# XC7A35TFTG256_bank15.net
KiCad netlist of a schematic drawn in Altium Designer
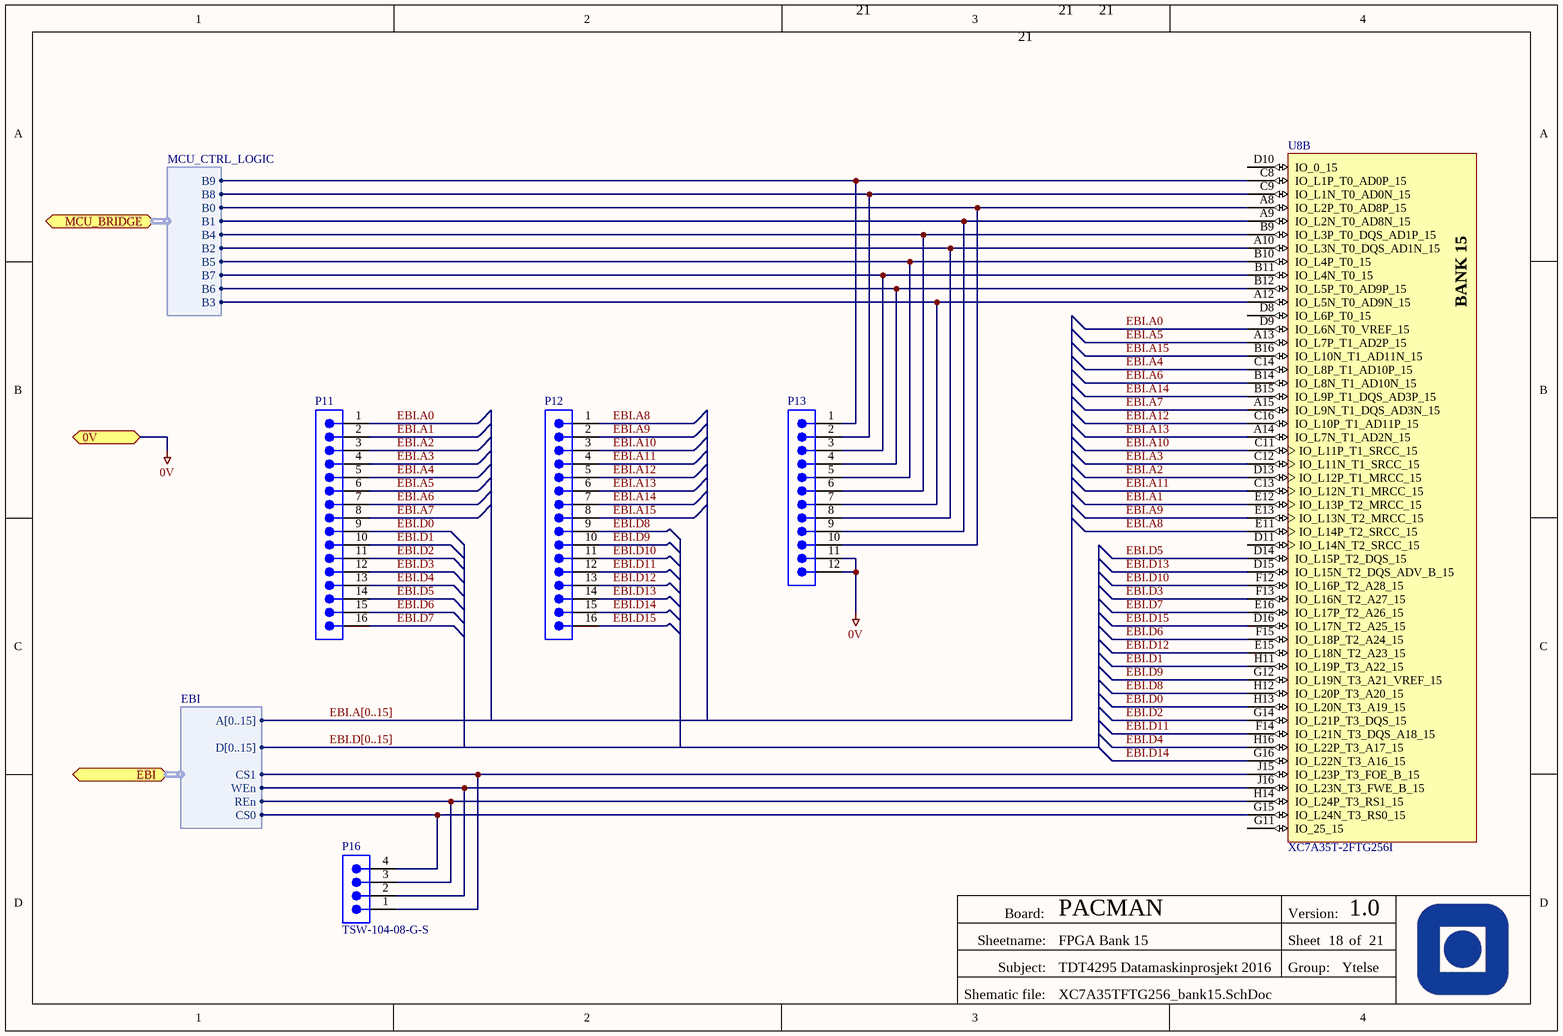
[diagram p0: XC7A35TFTG256_bank15.SchDoc]

(export (version "E")
  (design (tool "Eeschema 10.0.6"))
  (components
    (comp (ref "P11")
      (value "MTLW-116-07-F-S-265")
      (footprint "SMTC-MTLW-116-07-X-S-265")
      (fields (field (name "MANUFACTURER") "Samtec"))
      (libsource (lib "Altium Content Vault") (part "SMTC-MTLW-116-07-X-S-265"))
    )
    (comp (ref "P12")
      (value "MTLW-116-07-F-S-265")
      (footprint "SMTC-MTLW-116-07-X-S-265")
      (fields (field (name "MANUFACTURER") "Samtec"))
      (libsource (lib "Altium Content Vault") (part "SMTC-MTLW-116-07-X-S-265"))
    )
    (comp (ref "P13")
      (value "MTLW-112-07-L-S-125")
      (footprint "SMTC-MTLW-112-07-X-S-125")
      (fields (field (name "MANUFACTURER") "Samtec"))
      (libsource (lib "Altium Content Vault") (part "SMTC-MTLW-112-07-X-S-125"))
    )
    (comp (ref "P16")
      (value "TSW-104-08-G-S")
      (footprint "SMTC-TSW-104-08-X-S")
      (description "0.025\" SQ Post Header, Through-hole, Vertical, -55 to 125 degC, 2.54 mm Pitch, 4-Pin, Male, RoHS")
      (fields (field (name "MANUFACTURER") "Samtec"))
      (libsource (lib "Altium Content Vault") (part "SMTC-TSW-104-08-X-S"))
    )
    (comp (ref "U8")
      (value "XC7A35T-2FTG256I")
      (footprint "FTG256")
      (description "Artix-7 FPGA, 170 User I/Os, 0 GTP, 256-Ball BGA, Speed Grade 2, Industrial Grade, Pb-Free")
      (fields (field (name "MANUFACTURER") "Xilinx"))
      (libsource (lib "Altium Content Vault") (part "XLNX-XC7A35T-FTG256"))
    )
  )
  (nets
    (net (code "3") (name "/EBI.A0") (class "Default")
      (node (ref "P11") (pin "1") (pinfunction "1_1") (pintype "passive"))
      (node (ref "U8") (pin "D9") (pinfunction "IO_L6N_T0_VREF_15_D9") (pintype "bidirectional"))
    )
    (net (code "4") (name "/EBI.A1") (class "Default")
      (node (ref "P11") (pin "2") (pinfunction "2_2") (pintype "passive"))
      (node (ref "U8") (pin "E12") (pinfunction "IO_L13P_T2_MRCC_15_E12") (pintype "bidirectional"))
    )
    (net (code "5") (name "/EBI.A2") (class "Default")
      (node (ref "P11") (pin "3") (pinfunction "3_3") (pintype "passive"))
      (node (ref "U8") (pin "D13") (pinfunction "IO_L12P_T1_MRCC_15_D13") (pintype "bidirectional"))
    )
    (net (code "6") (name "/EBI.A3") (class "Default")
      (node (ref "P11") (pin "4") (pinfunction "4_4") (pintype "passive"))
      (node (ref "U8") (pin "C12") (pinfunction "IO_L11N_T1_SRCC_15_C12") (pintype "bidirectional"))
    )
    (net (code "7") (name "/EBI.A4") (class "Default")
      (node (ref "P11") (pin "5") (pinfunction "5_5") (pintype "passive"))
      (node (ref "U8") (pin "C14") (pinfunction "IO_L8P_T1_AD10P_15_C14") (pintype "bidirectional"))
    )
    (net (code "8") (name "/EBI.A5") (class "Default")
      (node (ref "P11") (pin "6") (pinfunction "6_6") (pintype "passive"))
      (node (ref "U8") (pin "A13") (pinfunction "IO_L7P_T1_AD2P_15_A13") (pintype "bidirectional"))
    )
    (net (code "9") (name "/EBI.A6") (class "Default")
      (node (ref "P11") (pin "7") (pinfunction "7_7") (pintype "passive"))
      (node (ref "U8") (pin "B14") (pinfunction "IO_L8N_T1_AD10N_15_B14") (pintype "bidirectional"))
    )
    (net (code "10") (name "/EBI.A7") (class "Default")
      (node (ref "P11") (pin "8") (pinfunction "8_8") (pintype "passive"))
      (node (ref "U8") (pin "A15") (pinfunction "IO_L9N_T1_DQS_AD3N_15_A15") (pintype "bidirectional"))
    )
    (net (code "11") (name "/EBI.A8") (class "Default")
      (node (ref "P12") (pin "1") (pinfunction "1_1") (pintype "passive"))
      (node (ref "U8") (pin "E11") (pinfunction "IO_L14P_T2_SRCC_15_E11") (pintype "bidirectional"))
    )
    (net (code "12") (name "/EBI.A9") (class "Default")
      (node (ref "P12") (pin "2") (pinfunction "2_2") (pintype "passive"))
      (node (ref "U8") (pin "E13") (pinfunction "IO_L13N_T2_MRCC_15_E13") (pintype "bidirectional"))
    )
    (net (code "13") (name "/EBI.A10") (class "Default")
      (node (ref "P12") (pin "3") (pinfunction "3_3") (pintype "passive"))
      (node (ref "U8") (pin "C11") (pinfunction "IO_L11P_T1_SRCC_15_C11") (pintype "bidirectional"))
    )
    (net (code "14") (name "/EBI.A11") (class "Default")
      (node (ref "P12") (pin "4") (pinfunction "4_4") (pintype "passive"))
      (node (ref "U8") (pin "C13") (pinfunction "IO_L12N_T1_MRCC_15_C13") (pintype "bidirectional"))
    )
    (net (code "15") (name "/EBI.A12") (class "Default")
      (node (ref "P12") (pin "5") (pinfunction "5_5") (pintype "passive"))
      (node (ref "U8") (pin "C16") (pinfunction "IO_L10P_T1_AD11P_15_C16") (pintype "bidirectional"))
    )
    (net (code "16") (name "/EBI.A13") (class "Default")
      (node (ref "P12") (pin "6") (pinfunction "6_6") (pintype "passive"))
      (node (ref "U8") (pin "A14") (pinfunction "IO_L7N_T1_AD2N_15_A14") (pintype "bidirectional"))
    )
    (net (code "17") (name "/EBI.A14") (class "Default")
      (node (ref "P12") (pin "7") (pinfunction "7_7") (pintype "passive"))
      (node (ref "U8") (pin "B15") (pinfunction "IO_L9P_T1_DQS_AD3P_15_B15") (pintype "bidirectional"))
    )
    (net (code "18") (name "/EBI.A15") (class "Default")
      (node (ref "P12") (pin "8") (pinfunction "8_8") (pintype "passive"))
      (node (ref "U8") (pin "B16") (pinfunction "IO_L10N_T1_AD11N_15_B16") (pintype "bidirectional"))
    )
    (net (code "20") (name "/EBI.D0") (class "Default")
      (node (ref "P11") (pin "9") (pinfunction "9_9") (pintype "passive"))
      (node (ref "U8") (pin "H13") (pinfunction "IO_L20N_T3_A19_15_H13") (pintype "bidirectional"))
    )
    (net (code "21") (name "/EBI.D1") (class "Default")
      (node (ref "P11") (pin "10") (pinfunction "10_10") (pintype "passive"))
      (node (ref "U8") (pin "H11") (pinfunction "IO_L19P_T3_A22_15_H11") (pintype "bidirectional"))
    )
    (net (code "22") (name "/EBI.D2") (class "Default")
      (node (ref "P11") (pin "11") (pinfunction "11_11") (pintype "passive"))
      (node (ref "U8") (pin "G14") (pinfunction "IO_L21P_T3_DQS_15_G14") (pintype "bidirectional"))
    )
    (net (code "23") (name "/EBI.D3") (class "Default")
      (node (ref "P11") (pin "12") (pinfunction "12_12") (pintype "passive"))
      (node (ref "U8") (pin "F13") (pinfunction "IO_L16N_T2_A27_15_F13") (pintype "bidirectional"))
    )
    (net (code "24") (name "/EBI.D4") (class "Default")
      (node (ref "P11") (pin "13") (pinfunction "13_13") (pintype "passive"))
      (node (ref "U8") (pin "H16") (pinfunction "IO_L22P_T3_A17_15_H16") (pintype "bidirectional"))
    )
    (net (code "25") (name "/EBI.D5") (class "Default")
      (node (ref "P11") (pin "14") (pinfunction "14_14") (pintype "passive"))
      (node (ref "U8") (pin "D14") (pinfunction "IO_L15P_T2_DQS_15_D14") (pintype "bidirectional"))
    )
    (net (code "26") (name "/EBI.D6") (class "Default")
      (node (ref "P11") (pin "15") (pinfunction "15_15") (pintype "passive"))
      (node (ref "U8") (pin "F15") (pinfunction "IO_L18P_T2_A24_15_F15") (pintype "bidirectional"))
    )
    (net (code "27") (name "/EBI.D7") (class "Default")
      (node (ref "P11") (pin "16") (pinfunction "16_16") (pintype "passive"))
      (node (ref "U8") (pin "E16") (pinfunction "IO_L17P_T2_A26_15_E16") (pintype "bidirectional"))
    )
    (net (code "28") (name "/EBI.D8") (class "Default")
      (node (ref "P12") (pin "9") (pinfunction "9_9") (pintype "passive"))
      (node (ref "U8") (pin "H12") (pinfunction "IO_L20P_T3_A20_15_H12") (pintype "bidirectional"))
    )
    (net (code "29") (name "/EBI.D9") (class "Default")
      (node (ref "P12") (pin "10") (pinfunction "10_10") (pintype "passive"))
      (node (ref "U8") (pin "G12") (pinfunction "IO_L19N_T3_A21_VREF_15_G12") (pintype "bidirectional"))
    )
    (net (code "30") (name "/EBI.D10") (class "Default")
      (node (ref "P12") (pin "11") (pinfunction "11_11") (pintype "passive"))
      (node (ref "U8") (pin "F12") (pinfunction "IO_L16P_T2_A28_15_F12") (pintype "bidirectional"))
    )
    (net (code "31") (name "/EBI.D11") (class "Default")
      (node (ref "P12") (pin "12") (pinfunction "12_12") (pintype "passive"))
      (node (ref "U8") (pin "F14") (pinfunction "IO_L21N_T3_DQS_A18_15_F14") (pintype "bidirectional"))
    )
    (net (code "32") (name "/EBI.D12") (class "Default")
      (node (ref "P12") (pin "13") (pinfunction "13_13") (pintype "passive"))
      (node (ref "U8") (pin "E15") (pinfunction "IO_L18N_T2_A23_15_E15") (pintype "bidirectional"))
    )
    (net (code "33") (name "/EBI.D13") (class "Default")
      (node (ref "P12") (pin "14") (pinfunction "14_14") (pintype "passive"))
      (node (ref "U8") (pin "D15") (pinfunction "IO_L15N_T2_DQS_ADV_B_15_D15") (pintype "bidirectional"))
    )
    (net (code "34") (name "/EBI.D14") (class "Default")
      (node (ref "P12") (pin "15") (pinfunction "15_15") (pintype "passive"))
      (node (ref "U8") (pin "G16") (pinfunction "IO_L22N_T3_A16_15_G16") (pintype "bidirectional"))
    )
    (net (code "35") (name "/EBI.D15") (class "Default")
      (node (ref "P12") (pin "16") (pinfunction "16_16") (pintype "passive"))
      (node (ref "U8") (pin "D16") (pinfunction "IO_L17N_T2_A25_15_D16") (pintype "bidirectional"))
    )
    (net (code "39") (name "0V") (class "Default")
      (node (ref "P13") (pin "11") (pinfunction "11_11") (pintype "passive"))
      (node (ref "P13") (pin "12") (pinfunction "12_12") (pintype "passive"))
    )
    (net (code "40") (name "Net-(U8B-IO_L1N_T0_AD0N_15)") (class "Default")
      (node (ref "P13") (pin "2") (pinfunction "2_2") (pintype "passive"))
      (node (ref "U8") (pin "C9") (pinfunction "IO_L1N_T0_AD0N_15_C9") (pintype "bidirectional"))
    )
    (net (code "41") (name "Net-(U8B-IO_L1P_T0_AD0P_15)") (class "Default")
      (node (ref "P13") (pin "1") (pinfunction "1_1") (pintype "passive"))
      (node (ref "U8") (pin "C8") (pinfunction "IO_L1P_T0_AD0P_15_C8") (pintype "bidirectional"))
    )
    (net (code "42") (name "Net-(U8B-IO_L2N_T0_AD8N_15)") (class "Default")
      (node (ref "P13") (pin "9") (pinfunction "9_9") (pintype "passive"))
      (node (ref "U8") (pin "A9") (pinfunction "IO_L2N_T0_AD8N_15_A9") (pintype "bidirectional"))
    )
    (net (code "43") (name "Net-(U8B-IO_L2P_T0_AD8P_15)") (class "Default")
      (node (ref "P13") (pin "10") (pinfunction "10_10") (pintype "passive"))
      (node (ref "U8") (pin "A8") (pinfunction "IO_L2P_T0_AD8P_15_A8") (pintype "bidirectional"))
    )
    (net (code "44") (name "Net-(U8B-IO_L3N_T0_DQS_AD1N_15)") (class "Default")
      (node (ref "P13") (pin "8") (pinfunction "8_8") (pintype "passive"))
      (node (ref "U8") (pin "A10") (pinfunction "IO_L3N_T0_DQS_AD1N_15_A10") (pintype "bidirectional"))
    )
    (net (code "45") (name "Net-(U8B-IO_L3P_T0_DQS_AD1P_15)") (class "Default")
      (node (ref "P13") (pin "6") (pinfunction "6_6") (pintype "passive"))
      (node (ref "U8") (pin "B9") (pinfunction "IO_L3P_T0_DQS_AD1P_15_B9") (pintype "bidirectional"))
    )
    (net (code "46") (name "Net-(U8B-IO_L4N_T0_15)") (class "Default")
      (node (ref "P13") (pin "3") (pinfunction "3_3") (pintype "passive"))
      (node (ref "U8") (pin "B11") (pinfunction "IO_L4N_T0_15_B11") (pintype "bidirectional"))
    )
    (net (code "47") (name "Net-(U8B-IO_L4P_T0_15)") (class "Default")
      (node (ref "P13") (pin "5") (pinfunction "5_5") (pintype "passive"))
      (node (ref "U8") (pin "B10") (pinfunction "IO_L4P_T0_15_B10") (pintype "bidirectional"))
    )
    (net (code "48") (name "Net-(U8B-IO_L5N_T0_AD9N_15)") (class "Default")
      (node (ref "P13") (pin "7") (pinfunction "7_7") (pintype "passive"))
      (node (ref "U8") (pin "A12") (pinfunction "IO_L5N_T0_AD9N_15_A12") (pintype "bidirectional"))
    )
    (net (code "49") (name "Net-(U8B-IO_L5P_T0_AD9P_15)") (class "Default")
      (node (ref "P13") (pin "4") (pinfunction "4_4") (pintype "passive"))
      (node (ref "U8") (pin "B12") (pinfunction "IO_L5P_T0_AD9P_15_B12") (pintype "bidirectional"))
    )
    (net (code "50") (name "Net-(U8B-IO_L23N_T3_FWE_B_15)") (class "Default")
      (node (ref "P16") (pin "2") (pinfunction "2_2") (pintype "passive"))
      (node (ref "U8") (pin "J16") (pinfunction "IO_L23N_T3_FWE_B_15_J16") (pintype "bidirectional"))
    )
    (net (code "51") (name "Net-(U8B-IO_L23P_T3_FOE_B_15)") (class "Default")
      (node (ref "P16") (pin "1") (pinfunction "1_1") (pintype "passive"))
      (node (ref "U8") (pin "J15") (pinfunction "IO_L23P_T3_FOE_B_15_J15") (pintype "bidirectional"))
    )
    (net (code "52") (name "Net-(U8B-IO_L24N_T3_RS0_15)") (class "Default")
      (node (ref "P16") (pin "4") (pinfunction "4_4") (pintype "passive"))
      (node (ref "U8") (pin "G15") (pinfunction "IO_L24N_T3_RS0_15_G15") (pintype "bidirectional"))
    )
    (net (code "53") (name "Net-(U8B-IO_L24P_T3_RS1_15)") (class "Default")
      (node (ref "P16") (pin "3") (pinfunction "3_3") (pintype "passive"))
      (node (ref "U8") (pin "H14") (pinfunction "IO_L24P_T3_RS1_15_H14") (pintype "bidirectional"))
    )
    (net (code "54") (name "unconnected-(U8B-IO_0_15-PadD10)") (class "Default")
      (node (ref "U8") (pin "D10") (pinfunction "IO_0_15_D10") (pintype "bidirectional"))
    )
    (net (code "55") (name "unconnected-(U8B-IO_25_15-PadG11)") (class "Default")
      (node (ref "U8") (pin "G11") (pinfunction "IO_25_15_G11") (pintype "bidirectional"))
    )
    (net (code "56") (name "unconnected-(U8B-IO_L6P_T0_15-PadD8)") (class "Default")
      (node (ref "U8") (pin "D8") (pinfunction "IO_L6P_T0_15_D8") (pintype "bidirectional"))
    )
    (net (code "57") (name "unconnected-(U8B-IO_L14N_T2_SRCC_15-PadD11)") (class "Default")
      (node (ref "U8") (pin "D11") (pinfunction "IO_L14N_T2_SRCC_15_D11") (pintype "bidirectional"))
    )
  )
)
